# Panel.net
KiCad netlist of a schematic drawn in EAGLE
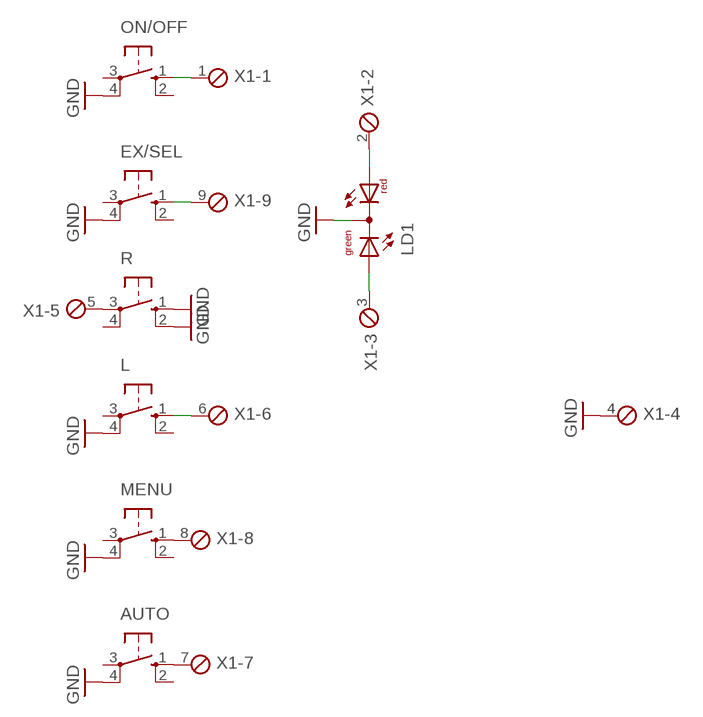
[diagram p0: schematic, sheet 1]

(export (version "E")
  (design (tool "Eeschema 10.0.6"))
  (components
    (comp (ref "AUTO")
      (value "10-XX")
      (footprint "eagle-import:B3F-10XX")
      (fields (field (name "MPN") "B3F-1000"))
      (libsource (lib "eagle-import") (part "10-XX"))
    )
    (comp (ref "EX/SEL")
      (value "10-XX")
      (footprint "eagle-import:B3F-10XX")
      (fields (field (name "MPN") "B3F-1000"))
      (libsource (lib "eagle-import") (part "10-XX"))
    )
    (comp (ref "L")
      (value "10-XX")
      (footprint "eagle-import:B3F-10XX")
      (fields (field (name "MPN") "B3F-1000"))
      (libsource (lib "eagle-import") (part "10-XX"))
    )
    (comp (ref "LD1")
      (value "DUOLED-RG-C")
      (footprint "eagle-import:DUOLED-C-5MM")
      (libsource (lib "eagle-import") (part "DUOLED-RG-C"))
    )
    (comp (ref "MENU")
      (value "10-XX")
      (footprint "eagle-import:B3F-10XX")
      (fields (field (name "MPN") "B3F-1000"))
      (libsource (lib "eagle-import") (part "10-XX"))
    )
    (comp (ref "ON/OFF")
      (value "10-XX")
      (footprint "eagle-import:B3F-10XX")
      (fields (field (name "MPN") "B3F-1000"))
      (libsource (lib "eagle-import") (part "10-XX"))
    )
    (comp (ref "R")
      (value "10-XX")
      (footprint "eagle-import:B3F-10XX")
      (fields (field (name "MPN") "B3F-1000"))
      (libsource (lib "eagle-import") (part "10-XX"))
    )
    (comp (ref "X1")
      (value "MPT9")
      (footprint "eagle-import:9POL254")
      (libsource (lib "eagle-import") (part "MPT9"))
    )
  )
  (nets
    (net (code "1") (name "GND") (class "Default")
      (node (ref "AUTO") (pin "4") (pinfunction "P1_4") (pintype "passive"))
      (node (ref "EX/SEL") (pin "4") (pinfunction "P1_4") (pintype "passive"))
      (node (ref "L") (pin "4") (pinfunction "P1_4") (pintype "passive"))
      (node (ref "LD1") (pin "C") (pinfunction "C_C") (pintype "passive"))
      (node (ref "MENU") (pin "4") (pinfunction "P1_4") (pintype "passive"))
      (node (ref "ON/OFF") (pin "4") (pinfunction "P1_4") (pintype "passive"))
      (node (ref "R") (pin "1") (pinfunction "S_1") (pintype "passive"))
      (node (ref "R") (pin "2") (pinfunction "S1_2") (pintype "passive"))
      (node (ref "X1") (pin "4") (pinfunction "1_4") (pintype "passive"))
    )
    (net (code "2") (name "Net-(AUTO-S)") (class "Default")
      (node (ref "AUTO") (pin "1") (pinfunction "S_1") (pintype "passive"))
      (node (ref "X1") (pin "7") (pinfunction "1_7") (pintype "passive"))
    )
    (net (code "3") (name "Net-(EX/SEL-S)") (class "Default")
      (node (ref "EX/SEL") (pin "1") (pinfunction "S_1") (pintype "passive"))
      (node (ref "X1") (pin "9") (pinfunction "1_9") (pintype "passive"))
    )
    (net (code "4") (name "Net-(L-S)") (class "Default")
      (node (ref "L") (pin "1") (pinfunction "S_1") (pintype "passive"))
      (node (ref "X1") (pin "6") (pinfunction "1_6") (pintype "passive"))
    )
    (net (code "5") (name "Net-(LD1-AG)") (class "Default")
      (node (ref "LD1") (pin "AX") (pinfunction "AG_AX") (pintype "passive"))
      (node (ref "X1") (pin "3") (pinfunction "1_3") (pintype "passive"))
    )
    (net (code "6") (name "Net-(MENU-S)") (class "Default")
      (node (ref "MENU") (pin "1") (pinfunction "S_1") (pintype "passive"))
      (node (ref "X1") (pin "8") (pinfunction "1_8") (pintype "passive"))
    )
    (net (code "7") (name "Net-(ON/OFF-S)") (class "Default")
      (node (ref "ON/OFF") (pin "1") (pinfunction "S_1") (pintype "passive"))
      (node (ref "X1") (pin "1") (pinfunction "1_1") (pintype "passive"))
    )
    (net (code "8") (name "Net-(R-P)") (class "Default")
      (node (ref "R") (pin "3") (pinfunction "P_3") (pintype "passive"))
      (node (ref "X1") (pin "5") (pinfunction "1_5") (pintype "passive"))
    )
    (net (code "9") (name "Net-(X1B-1)") (class "Default")
      (node (ref "LD1") (pin "AR") (pinfunction "AR_AR") (pintype "passive"))
      (node (ref "X1") (pin "2") (pinfunction "1_2") (pintype "passive"))
    )
    (net (code "10") (name "unconnected-(AUTO-P-Pad3)") (class "Default")
      (node (ref "AUTO") (pin "3") (pinfunction "P_3") (pintype "passive"))
    )
    (net (code "11") (name "unconnected-(AUTO-S1-Pad2)") (class "Default")
      (node (ref "AUTO") (pin "2") (pinfunction "S1_2") (pintype "passive"))
    )
    (net (code "12") (name "unconnected-(EX/SEL-P-Pad3)") (class "Default")
      (node (ref "EX/SEL") (pin "3") (pinfunction "P_3") (pintype "passive"))
    )
    (net (code "13") (name "unconnected-(EX/SEL-S1-Pad2)") (class "Default")
      (node (ref "EX/SEL") (pin "2") (pinfunction "S1_2") (pintype "passive"))
    )
    (net (code "14") (name "unconnected-(L-P-Pad3)") (class "Default")
      (node (ref "L") (pin "3") (pinfunction "P_3") (pintype "passive"))
    )
    (net (code "15") (name "unconnected-(L-S1-Pad2)") (class "Default")
      (node (ref "L") (pin "2") (pinfunction "S1_2") (pintype "passive"))
    )
    (net (code "16") (name "unconnected-(MENU-P-Pad3)") (class "Default")
      (node (ref "MENU") (pin "3") (pinfunction "P_3") (pintype "passive"))
    )
    (net (code "17") (name "unconnected-(MENU-S1-Pad2)") (class "Default")
      (node (ref "MENU") (pin "2") (pinfunction "S1_2") (pintype "passive"))
    )
    (net (code "18") (name "unconnected-(ON/OFF-P-Pad3)") (class "Default")
      (node (ref "ON/OFF") (pin "3") (pinfunction "P_3") (pintype "passive"))
    )
    (net (code "19") (name "unconnected-(ON/OFF-S1-Pad2)") (class "Default")
      (node (ref "ON/OFF") (pin "2") (pinfunction "S1_2") (pintype "passive"))
    )
    (net (code "20") (name "unconnected-(R-P1-Pad4)") (class "Default")
      (node (ref "R") (pin "4") (pinfunction "P1_4") (pintype "passive"))
    )
  )
)
